# Drone_Remote_Schematic.net
KiCad netlist of a schematic drawn in Altium Designer
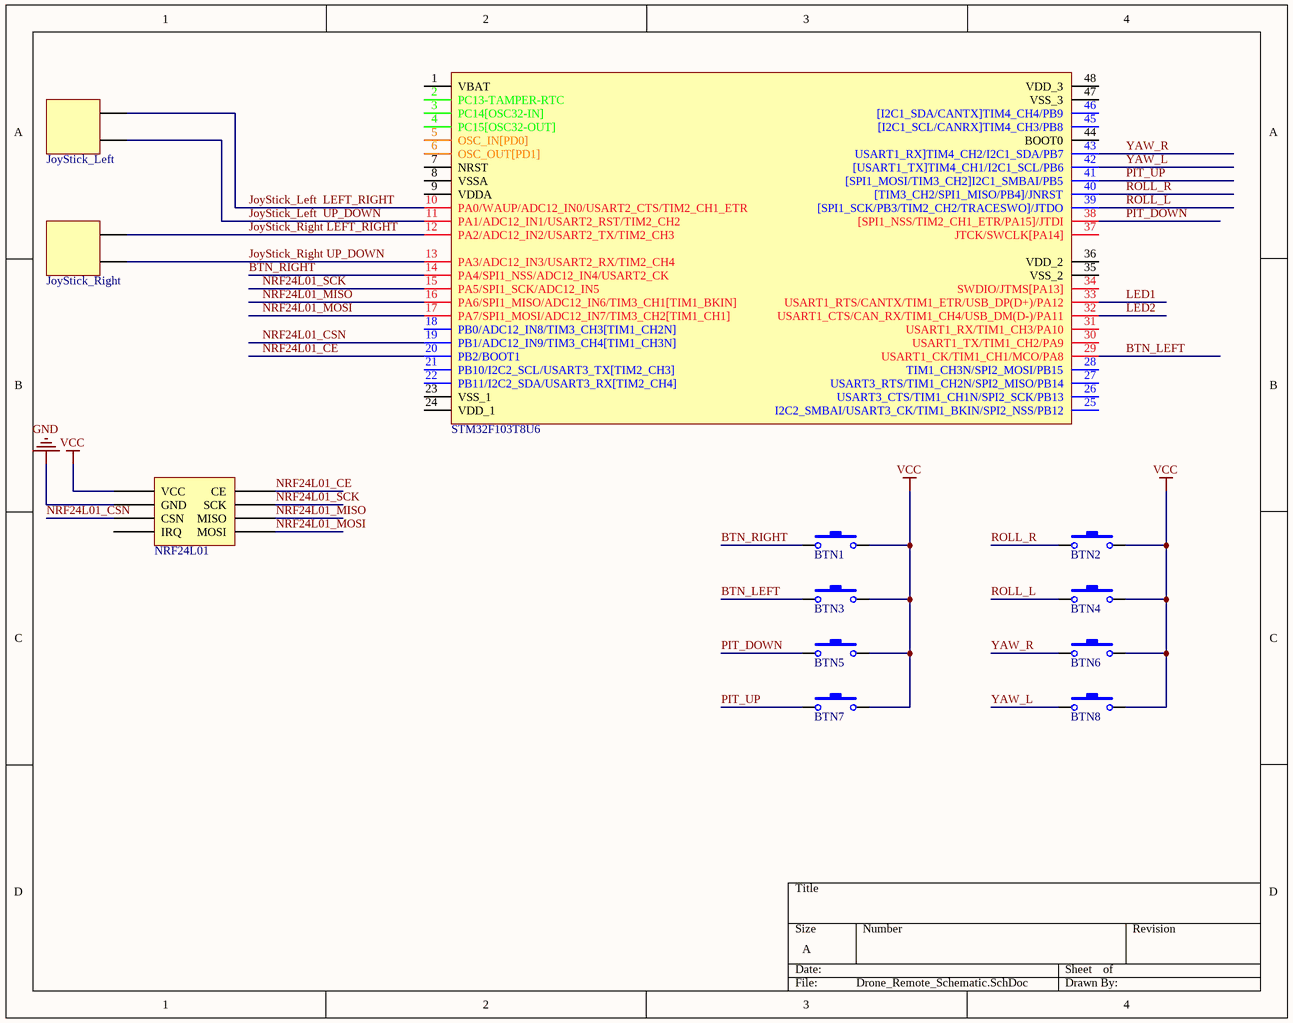
[diagram p0: Drone_Remote_Schematic.SchDoc]

(export (version "E")
  (design (tool "Eeschema 10.0.6"))
  (components
    (comp (ref "*1") (value "JoyStick_Left") (libsource (lib "NRF24L01") (part "JoyStick")))
    (comp (ref "*2") (value "JoyStick_Right") (libsource (lib "NRF24L01") (part "JoyStick")))
    (comp (ref "*NRF1") (value "NRF24L01") (libsource (lib "NRF24L01") (part "NRF24L01")))
    (comp (ref "BTN1")
      (value "EVQ-21307K")
      (description "PANASONIC   EVQ-21307K   SWITCH, TACTILE, SPST-NO, 20mA, 15VDC")
      (fields (field (name "MANUFACTURER") "Panasonic"))
      (libsource (lib "Zeki_Lib") (part "BTN_2_Pin"))
    )
    (comp (ref "BTN2")
      (value "EVQ-21307K")
      (description "PANASONIC   EVQ-21307K   SWITCH, TACTILE, SPST-NO, 20mA, 15VDC")
      (fields (field (name "MANUFACTURER") "Panasonic"))
      (libsource (lib "Zeki_Lib") (part "BTN_2_Pin"))
    )
    (comp (ref "BTN3")
      (value "EVQ-21307K")
      (description "PANASONIC   EVQ-21307K   SWITCH, TACTILE, SPST-NO, 20mA, 15VDC")
      (fields (field (name "MANUFACTURER") "Panasonic"))
      (libsource (lib "Zeki_Lib") (part "BTN_2_Pin"))
    )
    (comp (ref "BTN4")
      (value "EVQ-21307K")
      (description "PANASONIC   EVQ-21307K   SWITCH, TACTILE, SPST-NO, 20mA, 15VDC")
      (fields (field (name "MANUFACTURER") "Panasonic"))
      (libsource (lib "Zeki_Lib") (part "BTN_2_Pin"))
    )
    (comp (ref "BTN5")
      (value "EVQ-21307K")
      (description "PANASONIC   EVQ-21307K   SWITCH, TACTILE, SPST-NO, 20mA, 15VDC")
      (fields (field (name "MANUFACTURER") "Panasonic"))
      (libsource (lib "Zeki_Lib") (part "BTN_2_Pin"))
    )
    (comp (ref "BTN6")
      (value "EVQ-21307K")
      (description "PANASONIC   EVQ-21307K   SWITCH, TACTILE, SPST-NO, 20mA, 15VDC")
      (fields (field (name "MANUFACTURER") "Panasonic"))
      (libsource (lib "Zeki_Lib") (part "BTN_2_Pin"))
    )
    (comp (ref "BTN7")
      (value "EVQ-21307K")
      (description "PANASONIC   EVQ-21307K   SWITCH, TACTILE, SPST-NO, 20mA, 15VDC")
      (fields (field (name "MANUFACTURER") "Panasonic"))
      (libsource (lib "Zeki_Lib") (part "BTN_2_Pin"))
    )
    (comp (ref "BTN8")
      (value "EVQ-21307K")
      (description "PANASONIC   EVQ-21307K   SWITCH, TACTILE, SPST-NO, 20mA, 15VDC")
      (fields (field (name "MANUFACTURER") "Panasonic"))
      (libsource (lib "Zeki_Lib") (part "BTN_2_Pin"))
    )
    (comp (ref "STM32F103T8U6")
      (value "MCU_STM32F103C8T6")
      (fields
        (field (name "MANUFACTURER") "STMicroelectronics")
        (field (name "MANUFACTURER PART NUMBER") "STM32F103C8T6")
      )
      (libsource (lib "Zeki_Lib") (part "MCU_STM32F103C8T6"))
    )
  )
  (nets
    (net (code "1") (name "/BTN_LEFT") (class "Default")
      (node (ref "BTN3") (pin "1") (pinfunction "1_1") (pintype "passive"))
      (node (ref "STM32F103T8U6") (pin "29") (pinfunction "USART1_CK/TIM1_CH1/MCO/PA8_29") (pintype "power_in"))
    )
    (net (code "2") (name "/BTN_RIGHT") (class "Default")
      (node (ref "BTN1") (pin "1") (pinfunction "1_1") (pintype "passive"))
      (node (ref "STM32F103T8U6") (pin "14") (pinfunction "PA4/SPI1_NSS/ADC12_IN4/USART2_CK_14") (pintype "power_in"))
    )
    (net (code "3") (name "/JoyStick_Left  LEFT_RIGHT") (class "Default")
      (node (ref "*1") (pin "39") (pinfunction "39_39") (pintype "passive"))
      (node (ref "STM32F103T8U6") (pin "10") (pinfunction "PA0/WAUP/ADC12_IN0/USART2_CTS/TIM2_CH1_ETR_10") (pintype "power_in"))
    )
    (net (code "4") (name "/JoyStick_Left  UP_DOWN") (class "Default")
      (node (ref "*1") (pin "40") (pinfunction "40_40") (pintype "passive"))
      (node (ref "STM32F103T8U6") (pin "11") (pinfunction "PA1/ADC12_IN1/USART2_RST/TIM2_CH2_11") (pintype "power_in"))
    )
    (net (code "5") (name "/JoyStick_Right LEFT_RIGHT") (class "Default")
      (node (ref "*2") (pin "39") (pinfunction "39_39") (pintype "passive"))
      (node (ref "STM32F103T8U6") (pin "12") (pinfunction "PA2/ADC12_IN2/USART2_TX/TIM2_CH3_12") (pintype "power_in"))
    )
    (net (code "6") (name "/JoyStick_Right UP_DOWN") (class "Default")
      (node (ref "*2") (pin "40") (pinfunction "40_40") (pintype "passive"))
      (node (ref "STM32F103T8U6") (pin "13") (pinfunction "PA3/ADC12_IN3/USART2_RX/TIM2_CH4_13") (pintype "power_in"))
    )
    (net (code "7") (name "/LED1") (class "Default")
      (node (ref "STM32F103T8U6") (pin "33") (pinfunction "USART1_RTS/CANTX/TIM1_ETR/USB_DP(D+)/PA12_33") (pintype "power_in"))
    )
    (net (code "8") (name "/LED2") (class "Default")
      (node (ref "STM32F103T8U6") (pin "32") (pinfunction "USART1_CTS/CAN_RX/TIM1_CH4/USB_DM(D-)/PA11_32") (pintype "power_in"))
    )
    (net (code "9") (name "/NRF24L01_CE") (class "Default")
      (node (ref "*NRF1") (pin "18") (pinfunction "CE_18") (pintype "passive"))
      (node (ref "STM32F103T8U6") (pin "20") (pinfunction "PB2/BOOT1_20") (pintype "power_in"))
    )
    (net (code "10") (name "/NRF24L01_CSN") (class "Default")
      (node (ref "*NRF1") (pin "24") (pinfunction "CSN_24") (pintype "passive"))
      (node (ref "STM32F103T8U6") (pin "19") (pinfunction "PB1/ADC12_IN9/TIM3_CH4[TIM1_CH3N]_19") (pintype "power_in"))
    )
    (net (code "11") (name "/NRF24L01_MISO") (class "Default")
      (node (ref "*NRF1") (pin "20") (pinfunction "MISO_20") (pintype "passive"))
      (node (ref "STM32F103T8U6") (pin "16") (pinfunction "PA6/SPI1_MISO/ADC12_IN6/TIM3_CH1[TIM1_BKIN]_16") (pintype "power_in"))
    )
    (net (code "12") (name "/NRF24L01_MOSI") (class "Default")
      (node (ref "*NRF1") (pin "21") (pinfunction "MOSI_21") (pintype "passive"))
      (node (ref "STM32F103T8U6") (pin "17") (pinfunction "PA7/SPI1_MOSI/ADC12_IN7/TIM3_CH2[TIM1_CH1]_17") (pintype "power_in"))
    )
    (net (code "13") (name "/NRF24L01_SCK") (class "Default")
      (node (ref "*NRF1") (pin "19") (pinfunction "SCK_19") (pintype "passive"))
      (node (ref "STM32F103T8U6") (pin "15") (pinfunction "PA5/SPI1_SCK/ADC12_IN5_15") (pintype "power_in"))
    )
    (net (code "14") (name "/PIT_DOWN") (class "Default")
      (node (ref "BTN5") (pin "1") (pinfunction "1_1") (pintype "passive"))
      (node (ref "STM32F103T8U6") (pin "38") (pinfunction "[SPI1_NSS/TIM2_CH1_ETR/PA15]/JTDI_38") (pintype "power_in"))
    )
    (net (code "15") (name "/PIT_UP") (class "Default")
      (node (ref "BTN7") (pin "1") (pinfunction "1_1") (pintype "passive"))
      (node (ref "STM32F103T8U6") (pin "41") (pinfunction "[SPI1_MOSI/TIM3_CH2]I2C1_SMBAI/PB5_41") (pintype "power_in"))
    )
    (net (code "16") (name "/ROLL_L") (class "Default")
      (node (ref "BTN4") (pin "1") (pinfunction "1_1") (pintype "passive"))
      (node (ref "STM32F103T8U6") (pin "39") (pinfunction "[SPI1_SCK/PB3/TIM2_CH2/TRACESWO]/JTDO_39") (pintype "power_in"))
    )
    (net (code "17") (name "/ROLL_R") (class "Default")
      (node (ref "BTN2") (pin "1") (pinfunction "1_1") (pintype "passive"))
      (node (ref "STM32F103T8U6") (pin "40") (pinfunction "[TIM3_CH2/SPI1_MISO/PB4]/JNRST_40") (pintype "power_in"))
    )
    (net (code "18") (name "/YAW_L") (class "Default")
      (node (ref "BTN8") (pin "1") (pinfunction "1_1") (pintype "passive"))
      (node (ref "STM32F103T8U6") (pin "42") (pinfunction "[USART1_TX]TIM4_CH1/I2C1_SCL/PB6_42") (pintype "power_in"))
    )
    (net (code "19") (name "/YAW_R") (class "Default")
      (node (ref "BTN6") (pin "1") (pinfunction "1_1") (pintype "passive"))
      (node (ref "STM32F103T8U6") (pin "43") (pinfunction "USART1_RX]TIM4_CH2/I2C1_SDA/PB7_43") (pintype "power_in"))
    )
    (net (code "20") (name "GND") (class "Default")
      (node (ref "*NRF1") (pin "23") (pinfunction "GND_23") (pintype "passive"))
    )
    (net (code "21") (name "VCC") (class "Default")
      (node (ref "*NRF1") (pin "22") (pinfunction "VCC_22") (pintype "passive"))
      (node (ref "BTN1") (pin "2") (pinfunction "2_2") (pintype "passive"))
      (node (ref "BTN2") (pin "2") (pinfunction "2_2") (pintype "passive"))
      (node (ref "BTN3") (pin "2") (pinfunction "2_2") (pintype "passive"))
      (node (ref "BTN4") (pin "2") (pinfunction "2_2") (pintype "passive"))
      (node (ref "BTN5") (pin "2") (pinfunction "2_2") (pintype "passive"))
      (node (ref "BTN6") (pin "2") (pinfunction "2_2") (pintype "passive"))
      (node (ref "BTN7") (pin "2") (pinfunction "2_2") (pintype "passive"))
      (node (ref "BTN8") (pin "2") (pinfunction "2_2") (pintype "passive"))
    )
    (net (code "22") (name "unconnected-(*NRF1-IRQ-Pad25)") (class "Default")
      (node (ref "*NRF1") (pin "25") (pinfunction "IRQ_25") (pintype "passive"))
    )
    (net (code "23") (name "unconnected-(STM32F103T8U6-BOOT0-Pad44)") (class "Default")
      (node (ref "STM32F103T8U6") (pin "44") (pinfunction "BOOT0_44") (pintype "power_in"))
    )
    (net (code "24") (name "unconnected-(STM32F103T8U6-I2C2_SMBAI{slash}USART3_CK{slash}TIM1_BKIN{slash}SPI2_NSS{slash}PB12-Pad25)") (class "Default")
      (node (ref "STM32F103T8U6") (pin "25") (pinfunction "I2C2_SMBAI/USART3_CK/TIM1_BKIN/SPI2_NSS/PB12_25") (pintype "power_in"))
    )
    (net (code "25") (name "unconnected-(STM32F103T8U6-JTCK{slash}SWCLK[PA14]-Pad37)") (class "Default")
      (node (ref "STM32F103T8U6") (pin "37") (pinfunction "JTCK/SWCLK[PA14]_37") (pintype "power_in"))
    )
    (net (code "26") (name "unconnected-(STM32F103T8U6-NRST-Pad7)") (class "Default")
      (node (ref "STM32F103T8U6") (pin "7") (pinfunction "NRST_7") (pintype "power_in"))
    )
    (net (code "27") (name "unconnected-(STM32F103T8U6-OSC_IN[PD0]-Pad5)") (class "Default")
      (node (ref "STM32F103T8U6") (pin "5") (pinfunction "OSC_IN[PD0]_5") (pintype "power_in"))
    )
    (net (code "28") (name "unconnected-(STM32F103T8U6-OSC_OUT[PD1]-Pad6)") (class "Default")
      (node (ref "STM32F103T8U6") (pin "6") (pinfunction "OSC_OUT[PD1]_6") (pintype "power_in"))
    )
    (net (code "29") (name "unconnected-(STM32F103T8U6-PB0{slash}ADC12_IN8{slash}TIM3_CH3[TIM1_CH2N]-Pad18)") (class "Default")
      (node (ref "STM32F103T8U6") (pin "18") (pinfunction "PB0/ADC12_IN8/TIM3_CH3[TIM1_CH2N]_18") (pintype "power_in"))
    )
    (net (code "30") (name "unconnected-(STM32F103T8U6-PB10{slash}I2C2_SCL{slash}USART3_TX[TIM2_CH3]-Pad21)") (class "Default")
      (node (ref "STM32F103T8U6") (pin "21") (pinfunction "PB10/I2C2_SCL/USART3_TX[TIM2_CH3]_21") (pintype "power_in"))
    )
    (net (code "31") (name "unconnected-(STM32F103T8U6-PB11{slash}I2C2_SDA{slash}USART3_RX[TIM2_CH4]-Pad22)") (class "Default")
      (node (ref "STM32F103T8U6") (pin "22") (pinfunction "PB11/I2C2_SDA/USART3_RX[TIM2_CH4]_22") (pintype "power_in"))
    )
    (net (code "32") (name "unconnected-(STM32F103T8U6-PC13-TAMPER-RTC-Pad2)") (class "Default")
      (node (ref "STM32F103T8U6") (pin "2") (pinfunction "PC13-TAMPER-RTC_2") (pintype "power_in"))
    )
    (net (code "33") (name "unconnected-(STM32F103T8U6-PC14[OSC32-IN]-Pad3)") (class "Default")
      (node (ref "STM32F103T8U6") (pin "3") (pinfunction "PC14[OSC32-IN]_3") (pintype "power_in"))
    )
    (net (code "34") (name "unconnected-(STM32F103T8U6-PC15[OSC32-OUT]-Pad4)") (class "Default")
      (node (ref "STM32F103T8U6") (pin "4") (pinfunction "PC15[OSC32-OUT]_4") (pintype "power_in"))
    )
    (net (code "35") (name "unconnected-(STM32F103T8U6-SWDIO{slash}JTMS[PA13]-Pad34)") (class "Default")
      (node (ref "STM32F103T8U6") (pin "34") (pinfunction "SWDIO/JTMS[PA13]_34") (pintype "power_in"))
    )
    (net (code "36") (name "unconnected-(STM32F103T8U6-TIM1_CH3N{slash}SPI2_MOSI{slash}PB15-Pad28)") (class "Default")
      (node (ref "STM32F103T8U6") (pin "28") (pinfunction "TIM1_CH3N/SPI2_MOSI/PB15_28") (pintype "power_in"))
    )
    (net (code "37") (name "unconnected-(STM32F103T8U6-USART1_RX{slash}TIM1_CH3{slash}PA10-Pad31)") (class "Default")
      (node (ref "STM32F103T8U6") (pin "31") (pinfunction "USART1_RX/TIM1_CH3/PA10_31") (pintype "power_in"))
    )
    (net (code "38") (name "unconnected-(STM32F103T8U6-USART1_TX{slash}TIM1_CH2{slash}PA9-Pad30)") (class "Default")
      (node (ref "STM32F103T8U6") (pin "30") (pinfunction "USART1_TX/TIM1_CH2/PA9_30") (pintype "power_in"))
    )
    (net (code "39") (name "unconnected-(STM32F103T8U6-USART3_CTS{slash}TIM1_CH1N{slash}SPI2_SCK{slash}PB13-Pad26)") (class "Default")
      (node (ref "STM32F103T8U6") (pin "26") (pinfunction "USART3_CTS/TIM1_CH1N/SPI2_SCK/PB13_26") (pintype "power_in"))
    )
    (net (code "40") (name "unconnected-(STM32F103T8U6-USART3_RTS{slash}TIM1_CH2N{slash}SPI2_MISO{slash}PB14-Pad27)") (class "Default")
      (node (ref "STM32F103T8U6") (pin "27") (pinfunction "USART3_RTS/TIM1_CH2N/SPI2_MISO/PB14_27") (pintype "power_in"))
    )
    (net (code "41") (name "unconnected-(STM32F103T8U6-VBAT-Pad1)") (class "Default")
      (node (ref "STM32F103T8U6") (pin "1") (pinfunction "VBAT_1") (pintype "power_in"))
    )
    (net (code "42") (name "unconnected-(STM32F103T8U6-VDDA-Pad9)") (class "Default")
      (node (ref "STM32F103T8U6") (pin "9") (pinfunction "VDDA_9") (pintype "power_in"))
    )
    (net (code "43") (name "unconnected-(STM32F103T8U6-VDD_1-Pad24)") (class "Default")
      (node (ref "STM32F103T8U6") (pin "24") (pinfunction "VDD_1_24") (pintype "power_in"))
    )
    (net (code "44") (name "unconnected-(STM32F103T8U6-VDD_2-Pad36)") (class "Default")
      (node (ref "STM32F103T8U6") (pin "36") (pinfunction "VDD_2_36") (pintype "power_in"))
    )
    (net (code "45") (name "unconnected-(STM32F103T8U6-VDD_3-Pad48)") (class "Default")
      (node (ref "STM32F103T8U6") (pin "48") (pinfunction "VDD_3_48") (pintype "power_in"))
    )
    (net (code "46") (name "unconnected-(STM32F103T8U6-VSSA-Pad8)") (class "Default")
      (node (ref "STM32F103T8U6") (pin "8") (pinfunction "VSSA_8") (pintype "power_in"))
    )
    (net (code "47") (name "unconnected-(STM32F103T8U6-VSS_1-Pad23)") (class "Default")
      (node (ref "STM32F103T8U6") (pin "23") (pinfunction "VSS_1_23") (pintype "power_in"))
    )
    (net (code "48") (name "unconnected-(STM32F103T8U6-VSS_2-Pad35)") (class "Default")
      (node (ref "STM32F103T8U6") (pin "35") (pinfunction "VSS_2_35") (pintype "power_in"))
    )
    (net (code "49") (name "unconnected-(STM32F103T8U6-VSS_3-Pad47)") (class "Default")
      (node (ref "STM32F103T8U6") (pin "47") (pinfunction "VSS_3_47") (pintype "power_in"))
    )
    (net (code "50") (name "unconnected-(STM32F103T8U6-[I2C1_SCL{slash}CANRX]TIM4_CH3{slash}PB8-Pad45)") (class "Default")
      (node (ref "STM32F103T8U6") (pin "45") (pinfunction "[I2C1_SCL/CANRX]TIM4_CH3/PB8_45") (pintype "power_in"))
    )
    (net (code "51") (name "unconnected-(STM32F103T8U6-[I2C1_SDA{slash}CANTX]TIM4_CH4{slash}PB9-Pad46)") (class "Default")
      (node (ref "STM32F103T8U6") (pin "46") (pinfunction "[I2C1_SDA/CANTX]TIM4_CH4/PB9_46") (pintype "power_in"))
    )
  )
)
